# Radio_Board.net
KiCad netlist of a schematic drawn in EAGLE
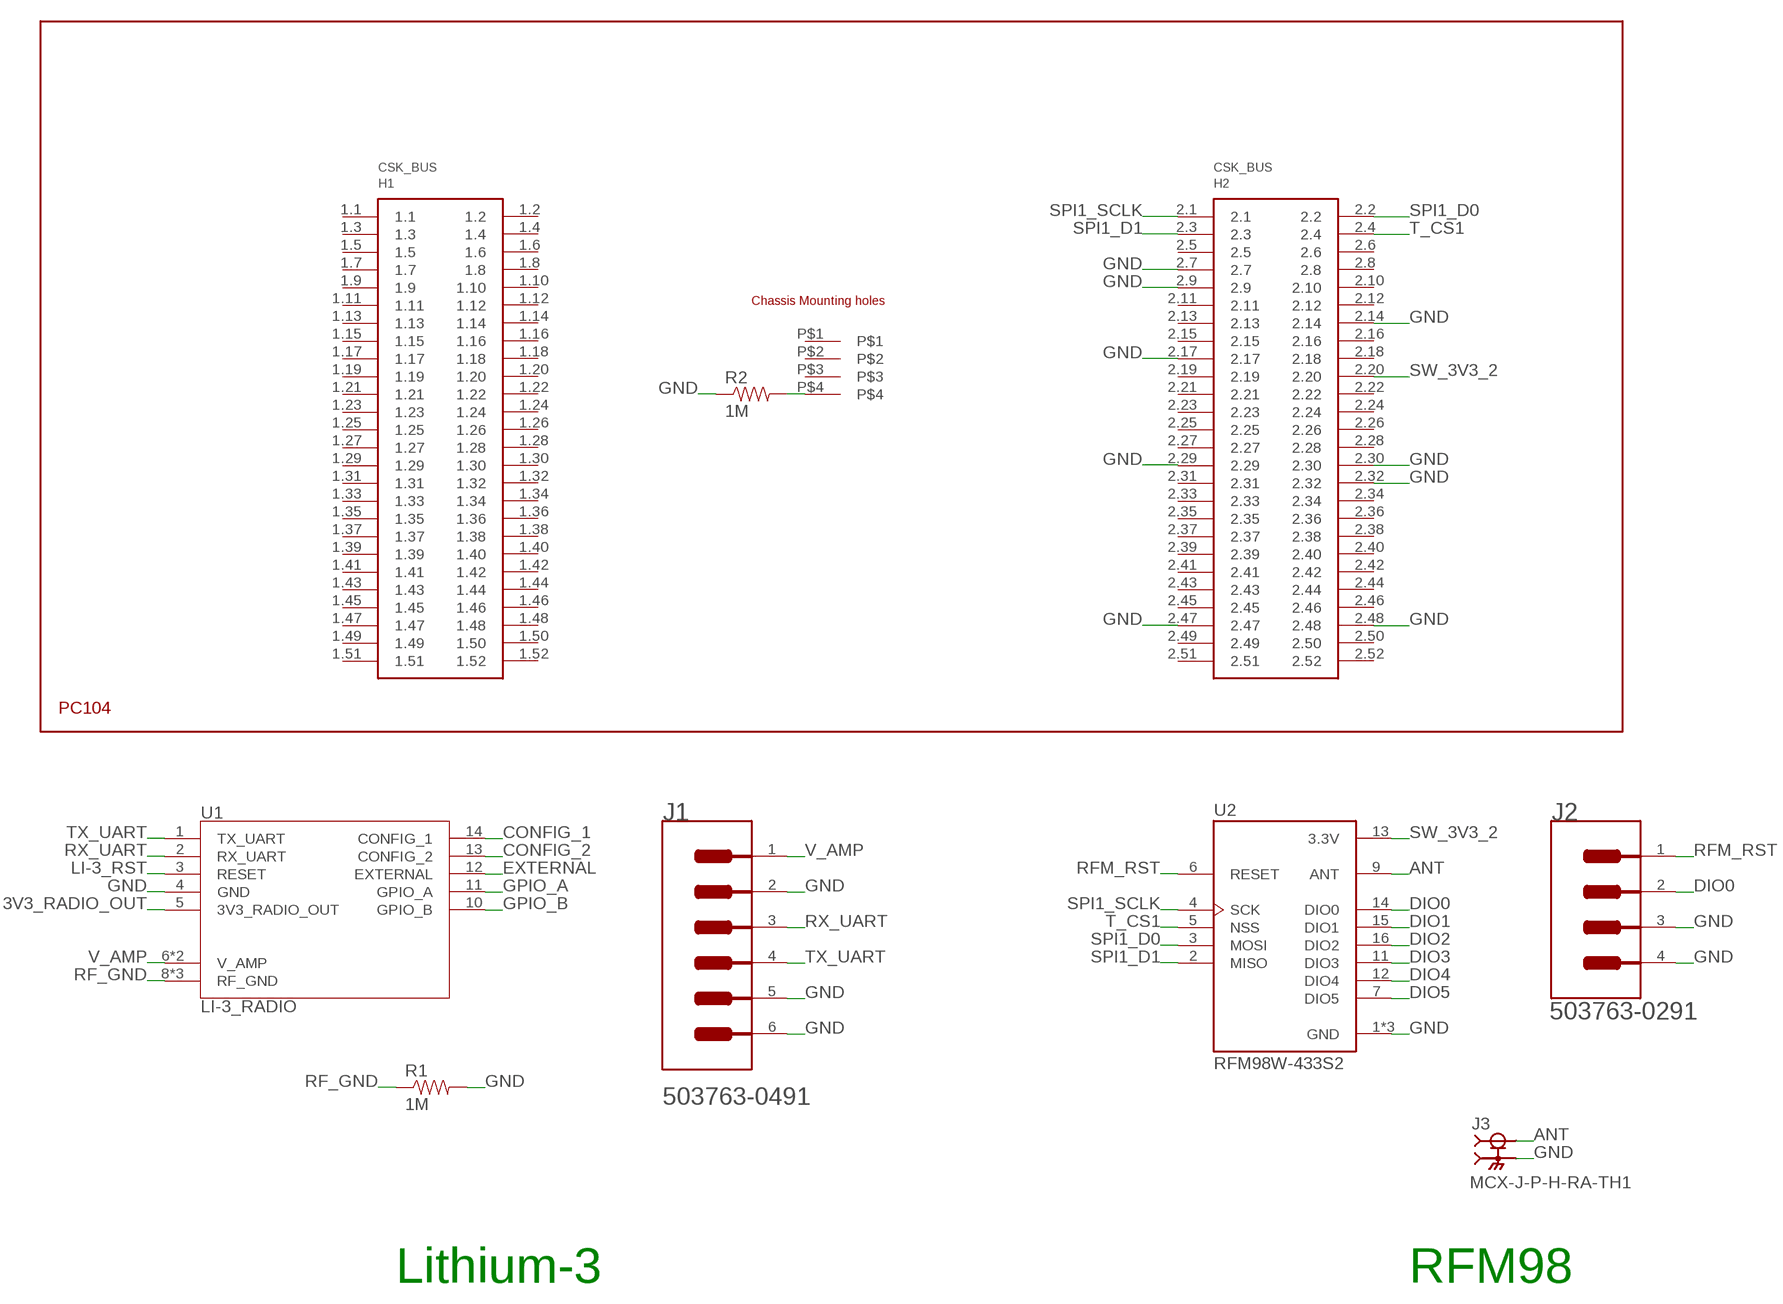
[diagram p0: schematic, sheet 1]

(export (version "E")
  (design (tool "Eeschema 10.0.6"))
  (components
    (comp (ref "H1")
      (value "PC104_WCONN")
      (footprint "eagle-import:PC104_WCONN")
      (libsource (lib "eagle-import") (part "PC104_WCONN"))
    )
    (comp (ref "J1")
      (value "MOLEX_503763-0491MOLEX_503763-0491_0_0")
      (footprint "eagle-import:MOLEX_503763-0491_0")
      (fields
        (field (name "DIGIKEY_PART_NUMBER") "WM10655CT-ND")
        (field (name "MF") "Molex")
        (field (name "MOUSER_PART_NUMBER") "538-503763-0491")
      )
      (libsource (lib "eagle-import") (part "MOLEX_503763-0491MOLEX_503763-0491_0_0"))
    )
    (comp (ref "J2")
      (value "MOLEX_503763-0291MOLEX_503763-0291_0_0")
      (footprint "eagle-import:MOLEX_503763-0291_0")
      (fields
        (field (name "DIGIKEY_PART_NUMBER") "WM10654CT-ND")
        (field (name "MF") "Molex")
        (field (name "MOUSER_PART_NUMBER") "538-503763-0291")
      )
      (libsource (lib "eagle-import") (part "MOLEX_503763-0291MOLEX_503763-0291_0_0"))
    )
    (comp (ref "J3")
      (value "MCX-J-P-H-RA-TH1")
      (footprint "eagle-import:SAMTEC_MCX-J-P-H-RA-TH1")
      (fields (field (name "DIGI-KEY_PART_NUMBER") "SAM10607-ND") (field (name "MF") "Samtec"))
      (libsource (lib "eagle-import") (part "MCX-J-P-H-RA-TH1"))
    )
    (comp (ref "R1")
      (value "1M")
      (footprint "eagle-import:0805")
      (libsource (lib "eagle-import") (part "RESISTOR0805-RES"))
    )
    (comp (ref "R2")
      (value "1M")
      (footprint "eagle-import:0805")
      (libsource (lib "eagle-import") (part "RESISTOR0805-RES"))
    )
    (comp (ref "U1")
      (value "LI-3_RADIO")
      (footprint "eagle-import:LI-3_RADIO")
      (libsource (lib "eagle-import") (part "LI-3_RADIO"))
    )
    (comp (ref "U2")
      (value "RFM98W-433S2")
      (footprint "eagle-import:RFM98W-433S2")
      (fields (field (name "MF") "RF Solutions"))
      (libsource (lib "eagle-import") (part "RFM98W-433S2"))
    )
  )
  (nets
    (net (code "1") (name "/3V3_RADIO_OUT") (class "Default")
      (node (ref "U1") (pin "5") (pinfunction "3V3_RADIO_OUT_5") (pintype "bidirectional"))
    )
    (net (code "2") (name "/ANT") (class "Default")
      (node (ref "J3") (pin "1") (pinfunction "1_1") (pintype "passive"))
      (node (ref "U2") (pin "9") (pinfunction "ANT_9") (pintype "bidirectional"))
    )
    (net (code "3") (name "/CONFIG_1") (class "Default")
      (node (ref "U1") (pin "14") (pinfunction "CONFIG_1_14") (pintype "bidirectional"))
    )
    (net (code "4") (name "/CONFIG_2") (class "Default")
      (node (ref "U1") (pin "13") (pinfunction "CONFIG_2_13") (pintype "bidirectional"))
    )
    (net (code "5") (name "/DIO0") (class "Default")
      (node (ref "J2") (pin "2") (pinfunction "2_2") (pintype "bidirectional"))
      (node (ref "U2") (pin "14") (pinfunction "DIO0_14") (pintype "bidirectional"))
    )
    (net (code "6") (name "/DIO1") (class "Default")
      (node (ref "U2") (pin "15") (pinfunction "DIO1_15") (pintype "bidirectional"))
    )
    (net (code "7") (name "/DIO2") (class "Default")
      (node (ref "U2") (pin "16") (pinfunction "DIO2_16") (pintype "bidirectional"))
    )
    (net (code "8") (name "/DIO3") (class "Default")
      (node (ref "U2") (pin "11") (pinfunction "DIO3_11") (pintype "bidirectional"))
    )
    (net (code "9") (name "/DIO4") (class "Default")
      (node (ref "U2") (pin "12") (pinfunction "DIO4_12") (pintype "bidirectional"))
    )
    (net (code "10") (name "/DIO5") (class "Default")
      (node (ref "U2") (pin "7") (pinfunction "DIO5_7") (pintype "bidirectional"))
    )
    (net (code "11") (name "/EXTERNAL") (class "Default")
      (node (ref "U1") (pin "12") (pinfunction "EXTERNAL_12") (pintype "bidirectional"))
    )
    (net (code "12") (name "/GND") (class "Default")
      (node (ref "H1") (pin "2.14") (pinfunction "2.14_2.14") (pintype "bidirectional"))
      (node (ref "H1") (pin "2.17") (pinfunction "2.17_2.17") (pintype "bidirectional"))
      (node (ref "H1") (pin "2.29") (pinfunction "2.29_2.29") (pintype "bidirectional"))
      (node (ref "H1") (pin "2.30") (pinfunction "2.30_2.30") (pintype "bidirectional"))
      (node (ref "H1") (pin "2.32") (pinfunction "2.32_2.32") (pintype "bidirectional"))
      (node (ref "H1") (pin "2.47") (pinfunction "2.47_2.47") (pintype "bidirectional"))
      (node (ref "H1") (pin "2.48") (pinfunction "2.48_2.48") (pintype "bidirectional"))
      (node (ref "H1") (pin "2.7") (pinfunction "2.7_2.7") (pintype "bidirectional"))
      (node (ref "H1") (pin "2.9") (pinfunction "2.9_2.9") (pintype "bidirectional"))
      (node (ref "J1") (pin "2") (pinfunction "2_2") (pintype "passive"))
      (node (ref "J1") (pin "5") (pinfunction "MNT_1_5") (pintype "passive"))
      (node (ref "J1") (pin "6") (pinfunction "MNT_2_6") (pintype "passive"))
      (node (ref "J2") (pin "3") (pinfunction "MNT_1_3") (pintype "bidirectional"))
      (node (ref "J2") (pin "4") (pinfunction "MNT_2_4") (pintype "bidirectional"))
      (node (ref "J3") (pin "S1") (pinfunction "2_S1") (pintype "passive"))
      (node (ref "J3") (pin "S2") (pinfunction "2_S2") (pintype "passive"))
      (node (ref "J3") (pin "S3") (pinfunction "2_S3") (pintype "passive"))
      (node (ref "J3") (pin "S4") (pinfunction "2_S4") (pintype "passive"))
      (node (ref "R1") (pin "2") (pinfunction "2_2") (pintype "passive"))
      (node (ref "R2") (pin "1") (pinfunction "1_1") (pintype "passive"))
      (node (ref "U1") (pin "4") (pinfunction "GND_4") (pintype "bidirectional"))
      (node (ref "U2") (pin "1") (pinfunction "GND_1") (pintype "power_in"))
      (node (ref "U2") (pin "10") (pinfunction "GND_10") (pintype "power_in"))
      (node (ref "U2") (pin "8") (pinfunction "GND_8") (pintype "power_in"))
    )
    (net (code "13") (name "/GPIO_A") (class "Default")
      (node (ref "U1") (pin "11") (pinfunction "GPIO_A_11") (pintype "bidirectional"))
    )
    (net (code "14") (name "/GPIO_B") (class "Default")
      (node (ref "U1") (pin "10") (pinfunction "GPIO_B_10") (pintype "bidirectional"))
    )
    (net (code "15") (name "/LI-3_RST") (class "Default")
      (node (ref "U1") (pin "3") (pinfunction "RESET_3") (pintype "bidirectional"))
    )
    (net (code "16") (name "/RFM_RST") (class "Default")
      (node (ref "J2") (pin "1") (pinfunction "1_1") (pintype "bidirectional"))
      (node (ref "U2") (pin "6") (pinfunction "RESET_6") (pintype "bidirectional"))
    )
    (net (code "17") (name "/RF_GND") (class "Default")
      (node (ref "R1") (pin "1") (pinfunction "1_1") (pintype "passive"))
      (node (ref "U1") (pin "15") (pinfunction "RF_GND_15") (pintype "bidirectional"))
      (node (ref "U1") (pin "8") (pinfunction "RF_GND_8") (pintype "bidirectional"))
      (node (ref "U1") (pin "9") (pinfunction "RF_GND_9") (pintype "bidirectional"))
    )
    (net (code "18") (name "/RX_UART") (class "Default")
      (node (ref "J1") (pin "3") (pinfunction "3_3") (pintype "passive"))
      (node (ref "U1") (pin "2") (pinfunction "RX_UART_2") (pintype "bidirectional"))
    )
    (net (code "19") (name "/SPI1_D0") (class "Default")
      (node (ref "H1") (pin "2.2") (pinfunction "2.2_2.2") (pintype "bidirectional"))
      (node (ref "U2") (pin "3") (pinfunction "MOSI_3") (pintype "input"))
    )
    (net (code "20") (name "/SPI1_D1") (class "Default")
      (node (ref "H1") (pin "2.3") (pinfunction "2.3_2.3") (pintype "bidirectional"))
      (node (ref "U2") (pin "2") (pinfunction "MISO_2") (pintype "output"))
    )
    (net (code "21") (name "/SPI1_SCLK") (class "Default")
      (node (ref "H1") (pin "2.1") (pinfunction "2.1_2.1") (pintype "bidirectional"))
      (node (ref "U2") (pin "4") (pinfunction "SCK_4") (pintype "input"))
    )
    (net (code "22") (name "/SW_3V3_2") (class "Default")
      (node (ref "H1") (pin "2.20") (pinfunction "2.20_2.20") (pintype "bidirectional"))
      (node (ref "U2") (pin "13") (pinfunction "3.3V_13") (pintype "power_in"))
    )
    (net (code "23") (name "/TX_UART") (class "Default")
      (node (ref "J1") (pin "4") (pinfunction "4_4") (pintype "passive"))
      (node (ref "U1") (pin "1") (pinfunction "TX_UART_1") (pintype "bidirectional"))
    )
    (net (code "24") (name "/T_CS1") (class "Default")
      (node (ref "H1") (pin "2.4") (pinfunction "2.4_2.4") (pintype "bidirectional"))
      (node (ref "U2") (pin "5") (pinfunction "NSS_5") (pintype "input"))
    )
    (net (code "25") (name "/V_AMP") (class "Default")
      (node (ref "J1") (pin "1") (pinfunction "1_1") (pintype "passive"))
      (node (ref "U1") (pin "6") (pinfunction "V_AMP_6") (pintype "bidirectional"))
      (node (ref "U1") (pin "7") (pinfunction "V_AMP_7") (pintype "bidirectional"))
    )
    (net (code "26") (name "Net-(H1-PadP$4)") (class "Default")
      (node (ref "H1") (pin "P$4") (pinfunction "P$4_P$4") (pintype "bidirectional"))
      (node (ref "R2") (pin "2") (pinfunction "2_2") (pintype "passive"))
    )
    (net (code "27") (name "unconnected-(H1-Pad1.1)") (class "Default")
      (node (ref "H1") (pin "1.1") (pinfunction "1.1_1.1") (pintype "bidirectional"))
    )
    (net (code "28") (name "unconnected-(H1-Pad1.2)") (class "Default")
      (node (ref "H1") (pin "1.2") (pinfunction "1.2_1.2") (pintype "bidirectional"))
    )
    (net (code "29") (name "unconnected-(H1-Pad1.3)") (class "Default")
      (node (ref "H1") (pin "1.3") (pinfunction "1.3_1.3") (pintype "bidirectional"))
    )
    (net (code "30") (name "unconnected-(H1-Pad1.4)") (class "Default")
      (node (ref "H1") (pin "1.4") (pinfunction "1.4_1.4") (pintype "bidirectional"))
    )
    (net (code "31") (name "unconnected-(H1-Pad1.5)") (class "Default")
      (node (ref "H1") (pin "1.5") (pinfunction "1.5_1.5") (pintype "bidirectional"))
    )
    (net (code "32") (name "unconnected-(H1-Pad1.6)") (class "Default")
      (node (ref "H1") (pin "1.6") (pinfunction "1.6_1.6") (pintype "bidirectional"))
    )
    (net (code "33") (name "unconnected-(H1-Pad1.7)") (class "Default")
      (node (ref "H1") (pin "1.7") (pinfunction "1.7_1.7") (pintype "bidirectional"))
    )
    (net (code "34") (name "unconnected-(H1-Pad1.8)") (class "Default")
      (node (ref "H1") (pin "1.8") (pinfunction "1.8_1.8") (pintype "bidirectional"))
    )
    (net (code "35") (name "unconnected-(H1-Pad1.9)") (class "Default")
      (node (ref "H1") (pin "1.9") (pinfunction "1.9_1.9") (pintype "bidirectional"))
    )
    (net (code "36") (name "unconnected-(H1-Pad1.10)") (class "Default")
      (node (ref "H1") (pin "1.10") (pinfunction "1.10_1.10") (pintype "bidirectional"))
    )
    (net (code "37") (name "unconnected-(H1-Pad1.11)") (class "Default")
      (node (ref "H1") (pin "1.11") (pinfunction "1.11_1.11") (pintype "bidirectional"))
    )
    (net (code "38") (name "unconnected-(H1-Pad1.12)") (class "Default")
      (node (ref "H1") (pin "1.12") (pinfunction "1.12_1.12") (pintype "bidirectional"))
    )
    (net (code "39") (name "unconnected-(H1-Pad1.13)") (class "Default")
      (node (ref "H1") (pin "1.13") (pinfunction "1.13_1.13") (pintype "bidirectional"))
    )
    (net (code "40") (name "unconnected-(H1-Pad1.14)") (class "Default")
      (node (ref "H1") (pin "1.14") (pinfunction "1.14_1.14") (pintype "bidirectional"))
    )
    (net (code "41") (name "unconnected-(H1-Pad1.15)") (class "Default")
      (node (ref "H1") (pin "1.15") (pinfunction "1.15_1.15") (pintype "bidirectional"))
    )
    (net (code "42") (name "unconnected-(H1-Pad1.16)") (class "Default")
      (node (ref "H1") (pin "1.16") (pinfunction "1.16_1.16") (pintype "bidirectional"))
    )
    (net (code "43") (name "unconnected-(H1-Pad1.17)") (class "Default")
      (node (ref "H1") (pin "1.17") (pinfunction "1.17_1.17") (pintype "bidirectional"))
    )
    (net (code "44") (name "unconnected-(H1-Pad1.18)") (class "Default")
      (node (ref "H1") (pin "1.18") (pinfunction "1.18_1.18") (pintype "bidirectional"))
    )
    (net (code "45") (name "unconnected-(H1-Pad1.19)") (class "Default")
      (node (ref "H1") (pin "1.19") (pinfunction "1.19_1.19") (pintype "bidirectional"))
    )
    (net (code "46") (name "unconnected-(H1-Pad1.20)") (class "Default")
      (node (ref "H1") (pin "1.20") (pinfunction "1.20_1.20") (pintype "bidirectional"))
    )
    (net (code "47") (name "unconnected-(H1-Pad1.21)") (class "Default")
      (node (ref "H1") (pin "1.21") (pinfunction "1.21_1.21") (pintype "bidirectional"))
    )
    (net (code "48") (name "unconnected-(H1-Pad1.22)") (class "Default")
      (node (ref "H1") (pin "1.22") (pinfunction "1.22_1.22") (pintype "bidirectional"))
    )
    (net (code "49") (name "unconnected-(H1-Pad1.23)") (class "Default")
      (node (ref "H1") (pin "1.23") (pinfunction "1.23_1.23") (pintype "bidirectional"))
    )
    (net (code "50") (name "unconnected-(H1-Pad1.24)") (class "Default")
      (node (ref "H1") (pin "1.24") (pinfunction "1.24_1.24") (pintype "bidirectional"))
    )
    (net (code "51") (name "unconnected-(H1-Pad1.25)") (class "Default")
      (node (ref "H1") (pin "1.25") (pinfunction "1.25_1.25") (pintype "bidirectional"))
    )
    (net (code "52") (name "unconnected-(H1-Pad1.26)") (class "Default")
      (node (ref "H1") (pin "1.26") (pinfunction "1.26_1.26") (pintype "bidirectional"))
    )
    (net (code "53") (name "unconnected-(H1-Pad1.27)") (class "Default")
      (node (ref "H1") (pin "1.27") (pinfunction "1.27_1.27") (pintype "bidirectional"))
    )
    (net (code "54") (name "unconnected-(H1-Pad1.28)") (class "Default")
      (node (ref "H1") (pin "1.28") (pinfunction "1.28_1.28") (pintype "bidirectional"))
    )
    (net (code "55") (name "unconnected-(H1-Pad1.29)") (class "Default")
      (node (ref "H1") (pin "1.29") (pinfunction "1.29_1.29") (pintype "bidirectional"))
    )
    (net (code "56") (name "unconnected-(H1-Pad1.30)") (class "Default")
      (node (ref "H1") (pin "1.30") (pinfunction "1.30_1.30") (pintype "bidirectional"))
    )
    (net (code "57") (name "unconnected-(H1-Pad1.31)") (class "Default")
      (node (ref "H1") (pin "1.31") (pinfunction "1.31_1.31") (pintype "bidirectional"))
    )
    (net (code "58") (name "unconnected-(H1-Pad1.32)") (class "Default")
      (node (ref "H1") (pin "1.32") (pinfunction "1.32_1.32") (pintype "bidirectional"))
    )
    (net (code "59") (name "unconnected-(H1-Pad1.33)") (class "Default")
      (node (ref "H1") (pin "1.33") (pinfunction "1.33_1.33") (pintype "bidirectional"))
    )
    (net (code "60") (name "unconnected-(H1-Pad1.34)") (class "Default")
      (node (ref "H1") (pin "1.34") (pinfunction "1.34_1.34") (pintype "bidirectional"))
    )
    (net (code "61") (name "unconnected-(H1-Pad1.35)") (class "Default")
      (node (ref "H1") (pin "1.35") (pinfunction "1.35_1.35") (pintype "bidirectional"))
    )
    (net (code "62") (name "unconnected-(H1-Pad1.36)") (class "Default")
      (node (ref "H1") (pin "1.36") (pinfunction "1.36_1.36") (pintype "bidirectional"))
    )
    (net (code "63") (name "unconnected-(H1-Pad1.37)") (class "Default")
      (node (ref "H1") (pin "1.37") (pinfunction "1.37_1.37") (pintype "bidirectional"))
    )
    (net (code "64") (name "unconnected-(H1-Pad1.38)") (class "Default")
      (node (ref "H1") (pin "1.38") (pinfunction "1.38_1.38") (pintype "bidirectional"))
    )
    (net (code "65") (name "unconnected-(H1-Pad1.39)") (class "Default")
      (node (ref "H1") (pin "1.39") (pinfunction "1.39_1.39") (pintype "bidirectional"))
    )
    (net (code "66") (name "unconnected-(H1-Pad1.40)") (class "Default")
      (node (ref "H1") (pin "1.40") (pinfunction "1.40_1.40") (pintype "bidirectional"))
    )
    (net (code "67") (name "unconnected-(H1-Pad1.41)") (class "Default")
      (node (ref "H1") (pin "1.41") (pinfunction "1.41_1.41") (pintype "bidirectional"))
    )
    (net (code "68") (name "unconnected-(H1-Pad1.42)") (class "Default")
      (node (ref "H1") (pin "1.42") (pinfunction "1.42_1.42") (pintype "bidirectional"))
    )
    (net (code "69") (name "unconnected-(H1-Pad1.43)") (class "Default")
      (node (ref "H1") (pin "1.43") (pinfunction "1.43_1.43") (pintype "bidirectional"))
    )
    (net (code "70") (name "unconnected-(H1-Pad1.44)") (class "Default")
      (node (ref "H1") (pin "1.44") (pinfunction "1.44_1.44") (pintype "bidirectional"))
    )
    (net (code "71") (name "unconnected-(H1-Pad1.45)") (class "Default")
      (node (ref "H1") (pin "1.45") (pinfunction "1.45_1.45") (pintype "bidirectional"))
    )
    (net (code "72") (name "unconnected-(H1-Pad1.46)") (class "Default")
      (node (ref "H1") (pin "1.46") (pinfunction "1.46_1.46") (pintype "bidirectional"))
    )
    (net (code "73") (name "unconnected-(H1-Pad1.47)") (class "Default")
      (node (ref "H1") (pin "1.47") (pinfunction "1.47_1.47") (pintype "bidirectional"))
    )
    (net (code "74") (name "unconnected-(H1-Pad1.48)") (class "Default")
      (node (ref "H1") (pin "1.48") (pinfunction "1.48_1.48") (pintype "bidirectional"))
    )
    (net (code "75") (name "unconnected-(H1-Pad1.49)") (class "Default")
      (node (ref "H1") (pin "1.49") (pinfunction "1.49_1.49") (pintype "bidirectional"))
    )
    (net (code "76") (name "unconnected-(H1-Pad1.50)") (class "Default")
      (node (ref "H1") (pin "1.50") (pinfunction "1.50_1.50") (pintype "bidirectional"))
    )
    (net (code "77") (name "unconnected-(H1-Pad1.51)") (class "Default")
      (node (ref "H1") (pin "1.51") (pinfunction "1.51_1.51") (pintype "bidirectional"))
    )
    (net (code "78") (name "unconnected-(H1-Pad1.52)") (class "Default")
      (node (ref "H1") (pin "1.52") (pinfunction "1.52_1.52") (pintype "bidirectional"))
    )
    (net (code "79") (name "unconnected-(H1-Pad2.5)") (class "Default")
      (node (ref "H1") (pin "2.5") (pinfunction "2.5_2.5") (pintype "bidirectional"))
    )
    (net (code "80") (name "unconnected-(H1-Pad2.6)") (class "Default")
      (node (ref "H1") (pin "2.6") (pinfunction "2.6_2.6") (pintype "bidirectional"))
    )
    (net (code "81") (name "unconnected-(H1-Pad2.8)") (class "Default")
      (node (ref "H1") (pin "2.8") (pinfunction "2.8_2.8") (pintype "bidirectional"))
    )
    (net (code "82") (name "unconnected-(H1-Pad2.10)") (class "Default")
      (node (ref "H1") (pin "2.10") (pinfunction "2.10_2.10") (pintype "bidirectional"))
    )
    (net (code "83") (name "unconnected-(H1-Pad2.11)") (class "Default")
      (node (ref "H1") (pin "2.11") (pinfunction "2.11_2.11") (pintype "bidirectional"))
    )
    (net (code "84") (name "unconnected-(H1-Pad2.12)") (class "Default")
      (node (ref "H1") (pin "2.12") (pinfunction "2.12_2.12") (pintype "bidirectional"))
    )
    (net (code "85") (name "unconnected-(H1-Pad2.13)") (class "Default")
      (node (ref "H1") (pin "2.13") (pinfunction "2.13_2.13") (pintype "bidirectional"))
    )
    (net (code "86") (name "unconnected-(H1-Pad2.15)") (class "Default")
      (node (ref "H1") (pin "2.15") (pinfunction "2.15_2.15") (pintype "bidirectional"))
    )
    (net (code "87") (name "unconnected-(H1-Pad2.16)") (class "Default")
      (node (ref "H1") (pin "2.16") (pinfunction "2.16_2.16") (pintype "bidirectional"))
    )
    (net (code "88") (name "unconnected-(H1-Pad2.18)") (class "Default")
      (node (ref "H1") (pin "2.18") (pinfunction "2.18_2.18") (pintype "bidirectional"))
    )
    (net (code "89") (name "unconnected-(H1-Pad2.19)") (class "Default")
      (node (ref "H1") (pin "2.19") (pinfunction "2.19_2.19") (pintype "bidirectional"))
    )
    (net (code "90") (name "unconnected-(H1-Pad2.21)") (class "Default")
      (node (ref "H1") (pin "2.21") (pinfunction "2.21_2.21") (pintype "bidirectional"))
    )
    (net (code "91") (name "unconnected-(H1-Pad2.22)") (class "Default")
      (node (ref "H1") (pin "2.22") (pinfunction "2.22_2.22") (pintype "bidirectional"))
    )
    (net (code "92") (name "unconnected-(H1-Pad2.23)") (class "Default")
      (node (ref "H1") (pin "2.23") (pinfunction "2.23_2.23") (pintype "bidirectional"))
    )
    (net (code "93") (name "unconnected-(H1-Pad2.24)") (class "Default")
      (node (ref "H1") (pin "2.24") (pinfunction "2.24_2.24") (pintype "bidirectional"))
    )
    (net (code "94") (name "unconnected-(H1-Pad2.25)") (class "Default")
      (node (ref "H1") (pin "2.25") (pinfunction "2.25_2.25") (pintype "bidirectional"))
    )
    (net (code "95") (name "unconnected-(H1-Pad2.26)") (class "Default")
      (node (ref "H1") (pin "2.26") (pinfunction "2.26_2.26") (pintype "bidirectional"))
    )
    (net (code "96") (name "unconnected-(H1-Pad2.27)") (class "Default")
      (node (ref "H1") (pin "2.27") (pinfunction "2.27_2.27") (pintype "bidirectional"))
    )
    (net (code "97") (name "unconnected-(H1-Pad2.28)") (class "Default")
      (node (ref "H1") (pin "2.28") (pinfunction "2.28_2.28") (pintype "bidirectional"))
    )
    (net (code "98") (name "unconnected-(H1-Pad2.31)") (class "Default")
      (node (ref "H1") (pin "2.31") (pinfunction "2.31_2.31") (pintype "bidirectional"))
    )
    (net (code "99") (name "unconnected-(H1-Pad2.33)") (class "Default")
      (node (ref "H1") (pin "2.33") (pinfunction "2.33_2.33") (pintype "bidirectional"))
    )
    (net (code "100") (name "unconnected-(H1-Pad2.34)") (class "Default")
      (node (ref "H1") (pin "2.34") (pinfunction "2.34_2.34") (pintype "bidirectional"))
    )
    (net (code "101") (name "unconnected-(H1-Pad2.35)") (class "Default")
      (node (ref "H1") (pin "2.35") (pinfunction "2.35_2.35") (pintype "bidirectional"))
    )
    (net (code "102") (name "unconnected-(H1-Pad2.36)") (class "Default")
      (node (ref "H1") (pin "2.36") (pinfunction "2.36_2.36") (pintype "bidirectional"))
    )
    (net (code "103") (name "unconnected-(H1-Pad2.37)") (class "Default")
      (node (ref "H1") (pin "2.37") (pinfunction "2.37_2.37") (pintype "bidirectional"))
    )
    (net (code "104") (name "unconnected-(H1-Pad2.38)") (class "Default")
      (node (ref "H1") (pin "2.38") (pinfunction "2.38_2.38") (pintype "bidirectional"))
    )
    (net (code "105") (name "unconnected-(H1-Pad2.39)") (class "Default")
      (node (ref "H1") (pin "2.39") (pinfunction "2.39_2.39") (pintype "bidirectional"))
    )
    (net (code "106") (name "unconnected-(H1-Pad2.40)") (class "Default")
      (node (ref "H1") (pin "2.40") (pinfunction "2.40_2.40") (pintype "bidirectional"))
    )
    (net (code "107") (name "unconnected-(H1-Pad2.41)") (class "Default")
      (node (ref "H1") (pin "2.41") (pinfunction "2.41_2.41") (pintype "bidirectional"))
    )
    (net (code "108") (name "unconnected-(H1-Pad2.42)") (class "Default")
      (node (ref "H1") (pin "2.42") (pinfunction "2.42_2.42") (pintype "bidirectional"))
    )
    (net (code "109") (name "unconnected-(H1-Pad2.43)") (class "Default")
      (node (ref "H1") (pin "2.43") (pinfunction "2.43_2.43") (pintype "bidirectional"))
    )
    (net (code "110") (name "unconnected-(H1-Pad2.44)") (class "Default")
      (node (ref "H1") (pin "2.44") (pinfunction "2.44_2.44") (pintype "bidirectional"))
    )
    (net (code "111") (name "unconnected-(H1-Pad2.45)") (class "Default")
      (node (ref "H1") (pin "2.45") (pinfunction "2.45_2.45") (pintype "bidirectional"))
    )
    (net (code "112") (name "unconnected-(H1-Pad2.46)") (class "Default")
      (node (ref "H1") (pin "2.46") (pinfunction "2.46_2.46") (pintype "bidirectional"))
    )
    (net (code "113") (name "unconnected-(H1-Pad2.49)") (class "Default")
      (node (ref "H1") (pin "2.49") (pinfunction "2.49_2.49") (pintype "bidirectional"))
    )
    (net (code "114") (name "unconnected-(H1-Pad2.50)") (class "Default")
      (node (ref "H1") (pin "2.50") (pinfunction "2.50_2.50") (pintype "bidirectional"))
    )
    (net (code "115") (name "unconnected-(H1-Pad2.51)") (class "Default")
      (node (ref "H1") (pin "2.51") (pinfunction "2.51_2.51") (pintype "bidirectional"))
    )
    (net (code "116") (name "unconnected-(H1-Pad2.52)") (class "Default")
      (node (ref "H1") (pin "2.52") (pinfunction "2.52_2.52") (pintype "bidirectional"))
    )
    (net (code "117") (name "unconnected-(H1-PadP$1)") (class "Default")
      (node (ref "H1") (pin "P$1") (pinfunction "P$1_P$1") (pintype "bidirectional"))
    )
    (net (code "118") (name "unconnected-(H1-PadP$2)") (class "Default")
      (node (ref "H1") (pin "P$2") (pinfunction "P$2_P$2") (pintype "bidirectional"))
    )
    (net (code "119") (name "unconnected-(H1-PadP$3)") (class "Default")
      (node (ref "H1") (pin "P$3") (pinfunction "P$3_P$3") (pintype "bidirectional"))
    )
  )
)
